# Vectr.net
KiCad netlist of a schematic drawn in EAGLE
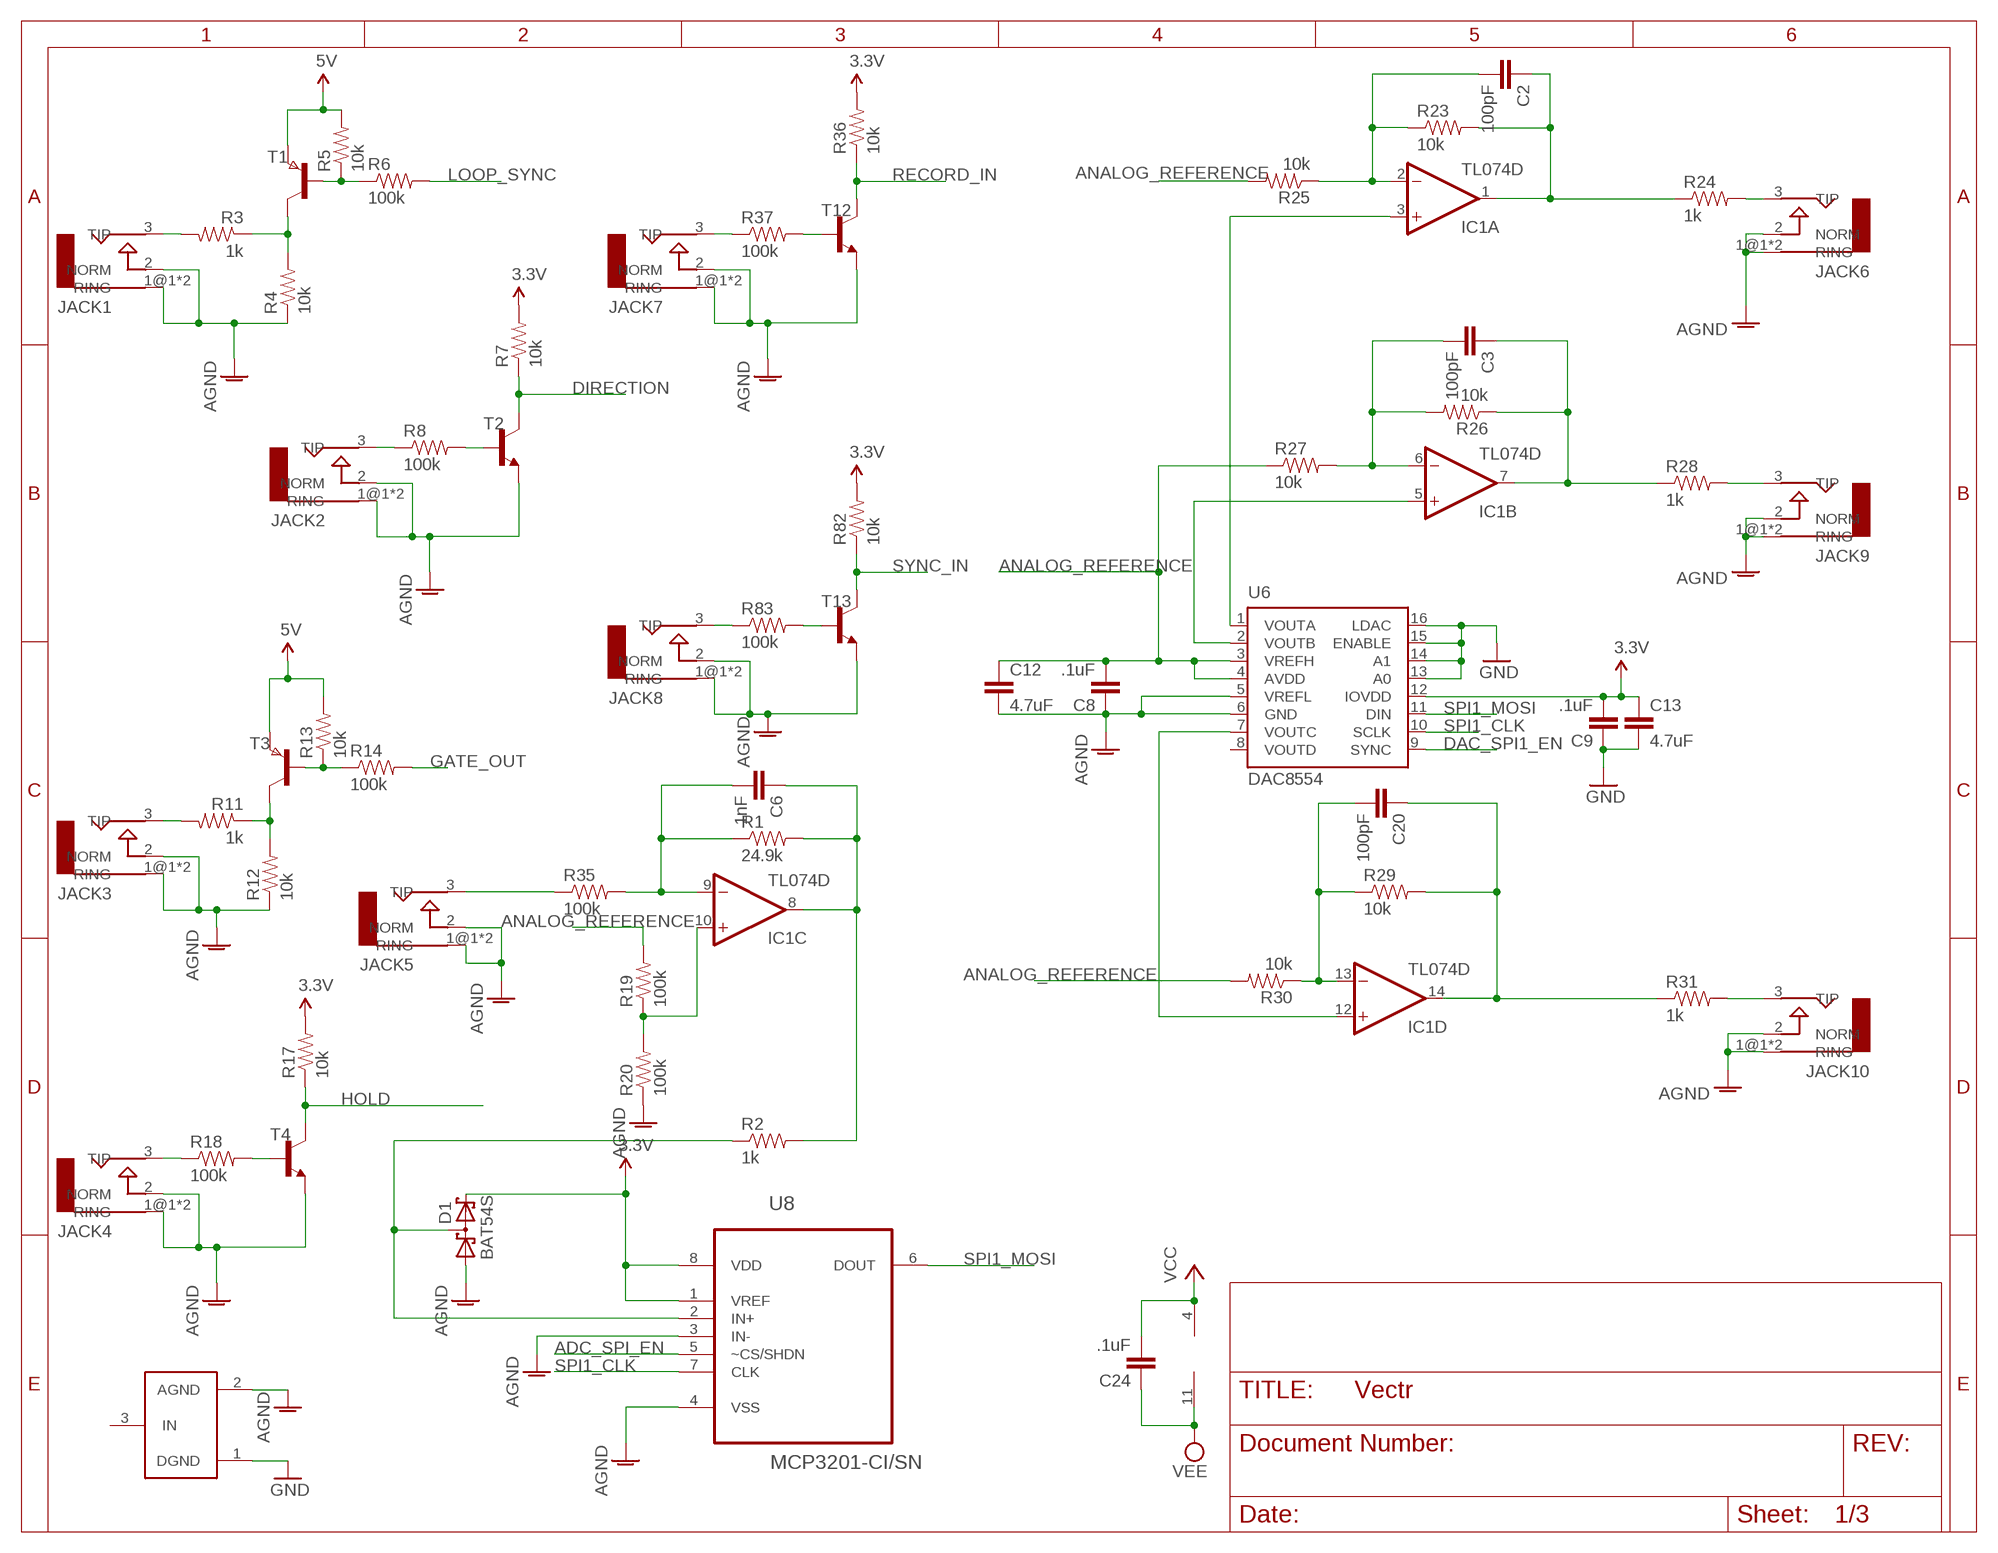
[diagram p0: schematic, sheet 1]
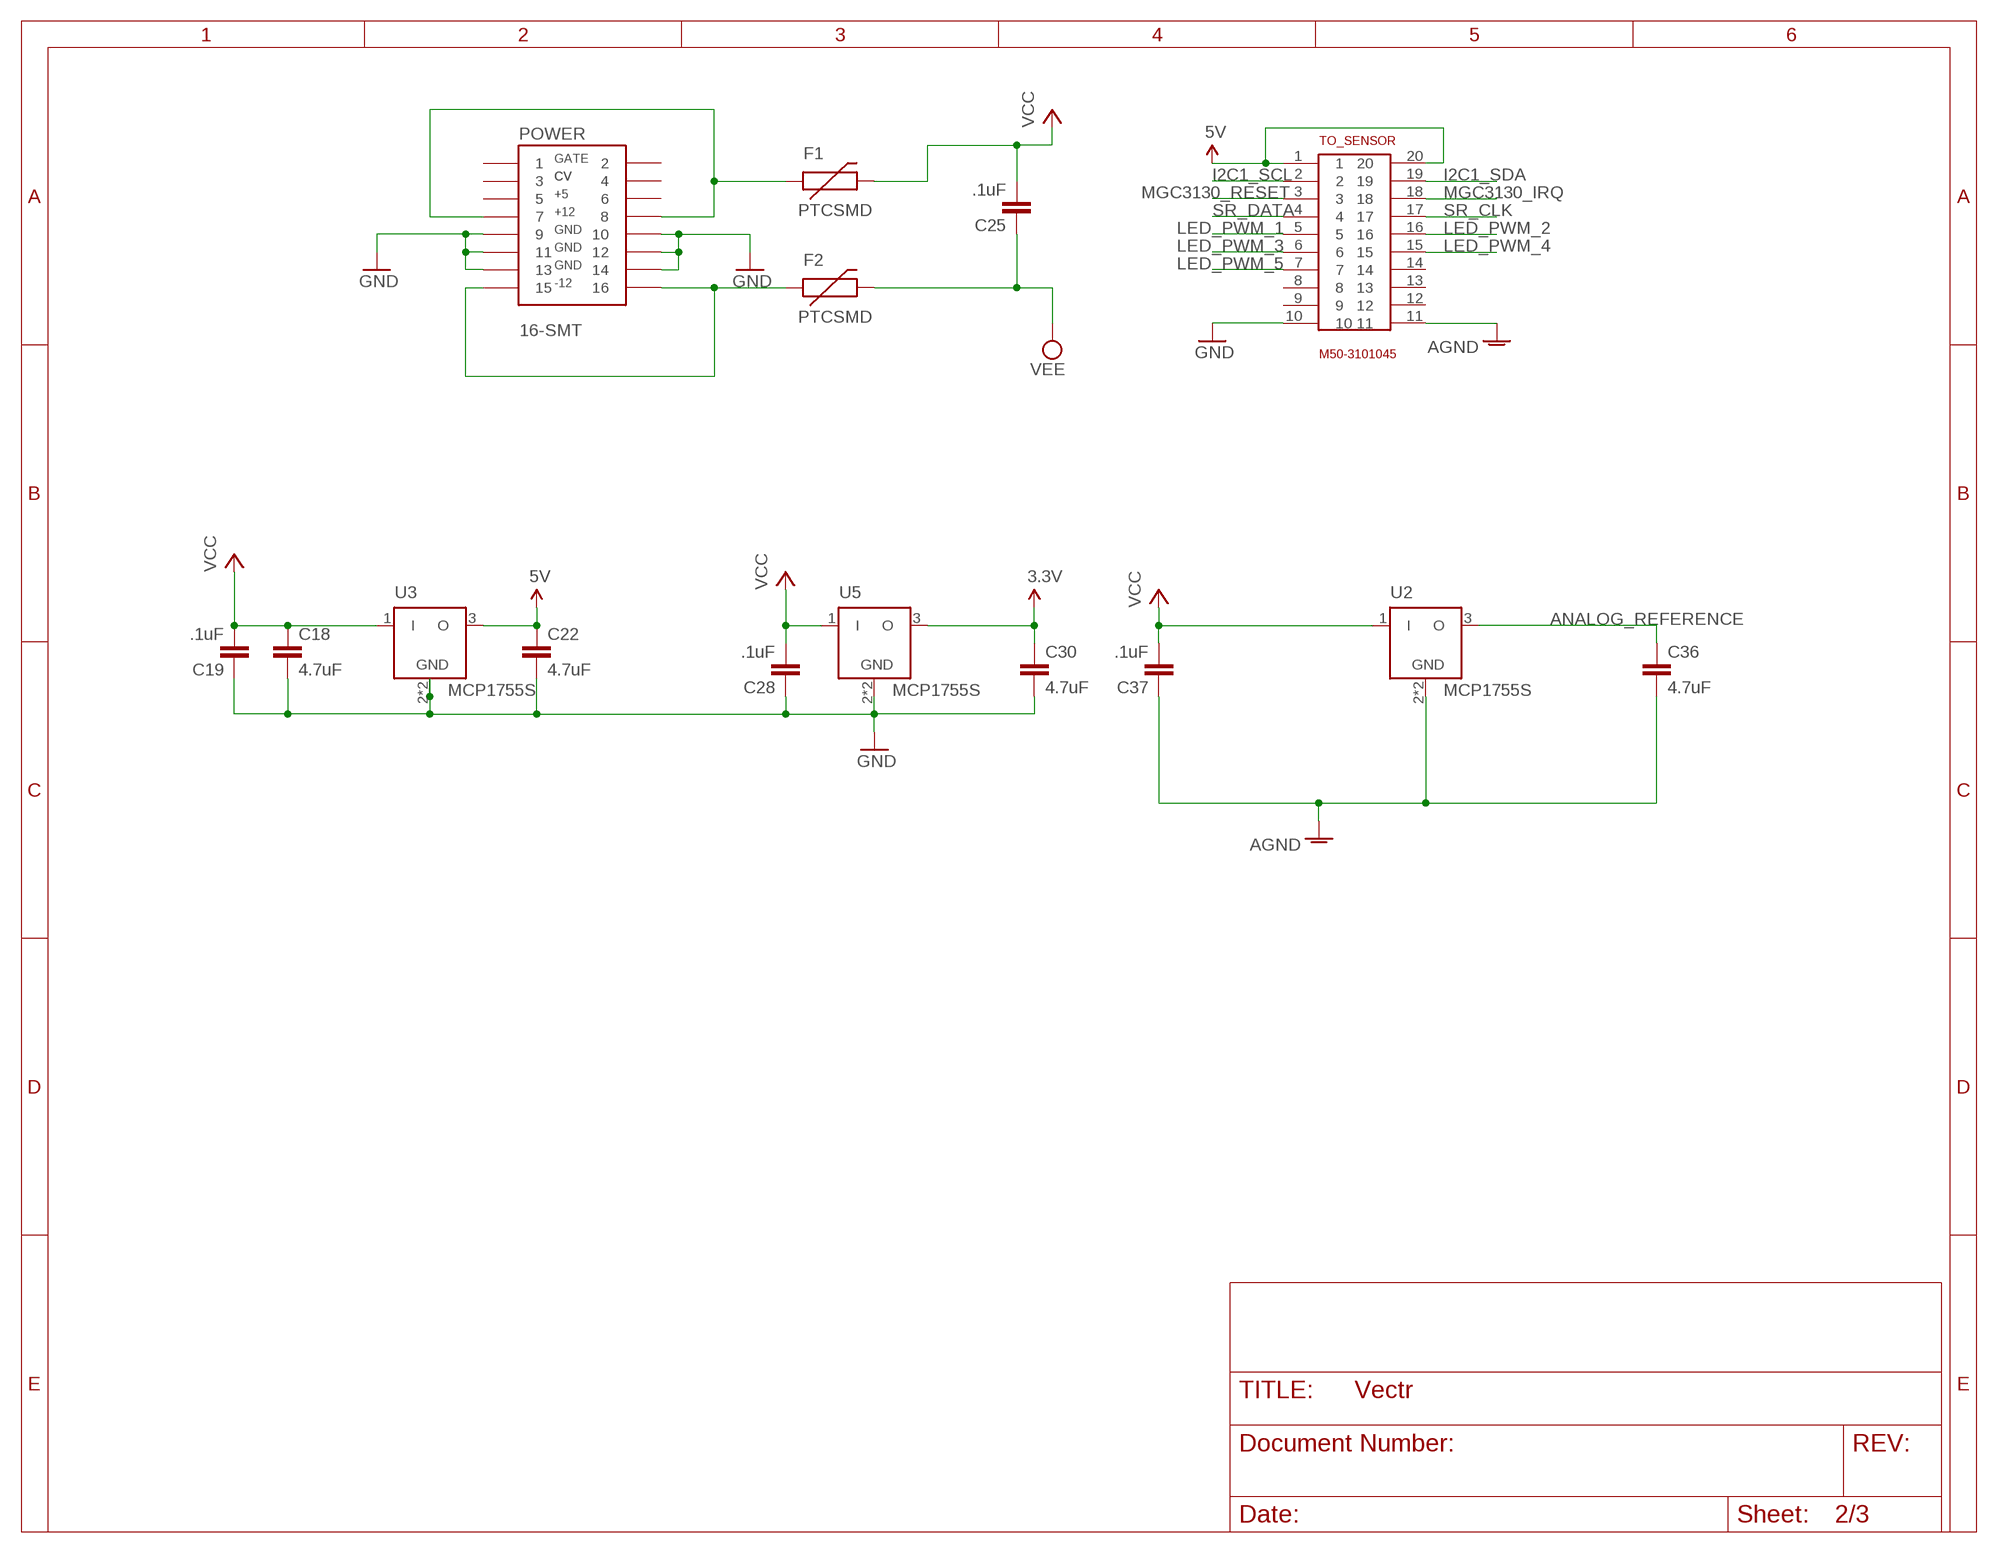
[diagram p1: schematic, sheet 2]
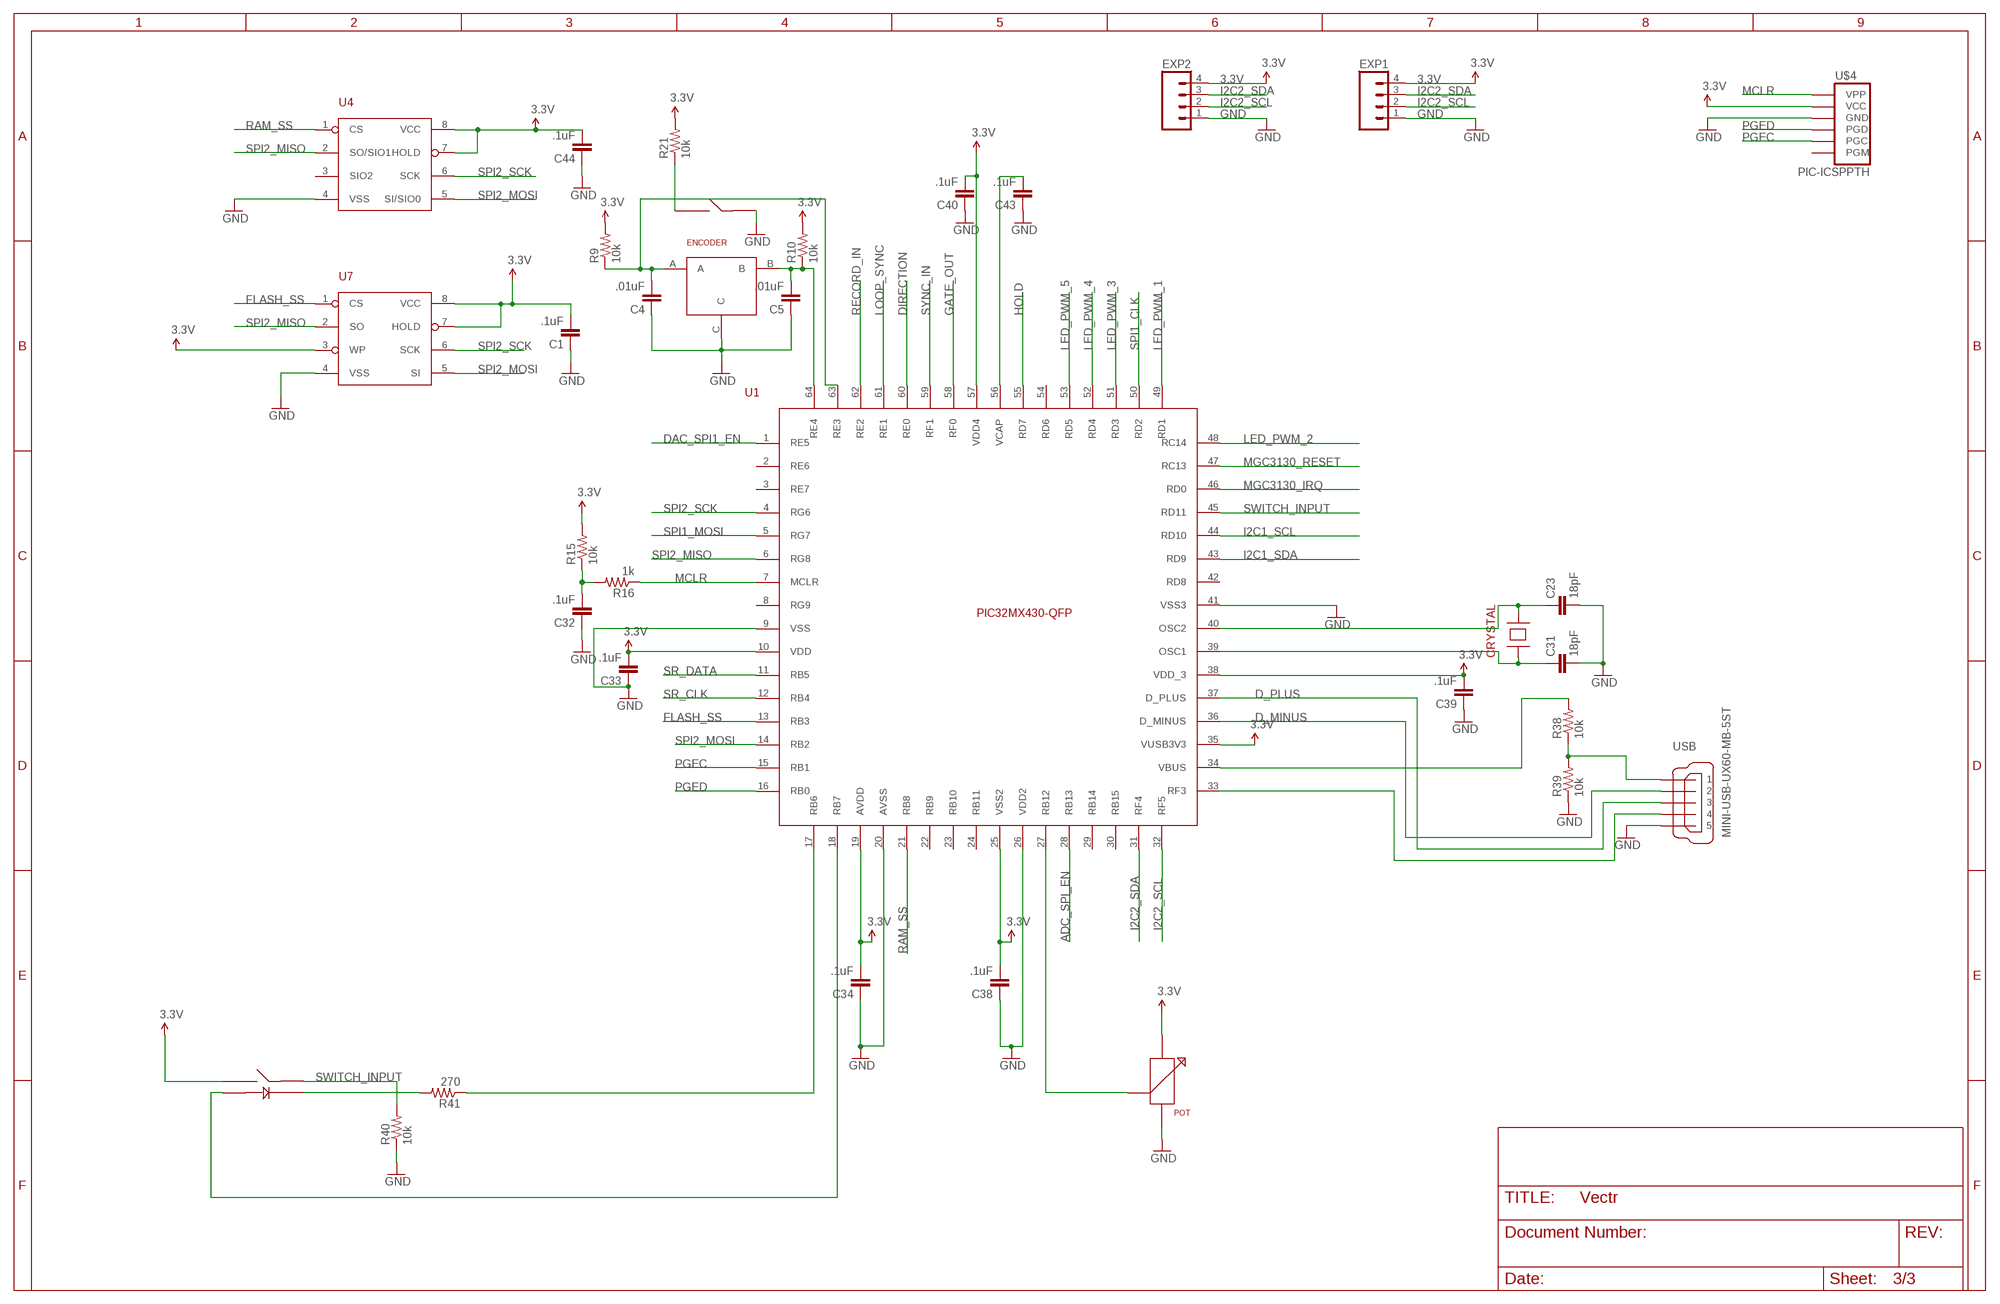
[diagram p2: schematic, sheet 3]

(export (version "E")
  (design (tool "Eeschema 10.0.6"))
  (components
    (comp (ref "C1")
      (value ".1uF")
      (footprint "eagle-import:0603-CAP")
      (libsource (lib "eagle-import") (part "SparkFun-Passives_CAP0603-CAP"))
    )
    (comp (ref "C4")
      (value ".01uF")
      (footprint "eagle-import:0603-CAP")
      (libsource (lib "eagle-import") (part "SparkFun-Passives_CAP0603-CAP"))
    )
    (comp (ref "C5")
      (value ".01uF")
      (footprint "eagle-import:0603-CAP")
      (libsource (lib "eagle-import") (part "SparkFun-Passives_CAP0603-CAP"))
    )
    (comp (ref "C23")
      (value "18pF")
      (footprint "eagle-import:0603-CAP")
      (libsource (lib "eagle-import") (part "SparkFun-Passives_CAP0603-CAP"))
    )
    (comp (ref "C31")
      (value "18pF")
      (footprint "eagle-import:0603-CAP")
      (libsource (lib "eagle-import") (part "SparkFun-Passives_CAP0603-CAP"))
    )
    (comp (ref "C32")
      (value ".1uF")
      (footprint "eagle-import:0603-CAP")
      (libsource (lib "eagle-import") (part "SparkFun-Passives_CAP0603-CAP"))
    )
    (comp (ref "C33")
      (value ".1uF")
      (footprint "eagle-import:0603-CAP")
      (libsource (lib "eagle-import") (part "SparkFun-Passives_CAP0603-CAP"))
    )
    (comp (ref "C34")
      (value ".1uF")
      (footprint "eagle-import:0603-CAP")
      (libsource (lib "eagle-import") (part "SparkFun-Passives_CAP0603-CAP"))
    )
    (comp (ref "C38")
      (value ".1uF")
      (footprint "eagle-import:0603-CAP")
      (libsource (lib "eagle-import") (part "SparkFun-Passives_CAP0603-CAP"))
    )
    (comp (ref "C39")
      (value ".1uF")
      (footprint "eagle-import:0603-CAP")
      (libsource (lib "eagle-import") (part "SparkFun-Passives_CAP0603-CAP"))
    )
    (comp (ref "C40")
      (value ".1uF")
      (footprint "eagle-import:0603-CAP")
      (libsource (lib "eagle-import") (part "SparkFun-Passives_CAP0603-CAP"))
    )
    (comp (ref "C43")
      (value ".1uF")
      (footprint "eagle-import:0603-CAP")
      (libsource (lib "eagle-import") (part "SparkFun-Passives_CAP0603-CAP"))
    )
    (comp (ref "C44")
      (value ".1uF")
      (footprint "eagle-import:0603-CAP")
      (libsource (lib "eagle-import") (part "SparkFun-Passives_CAP0603-CAP"))
    )
    (comp (ref "CRYSTAL")
      (value "SMD-4-CRYSTAL")
      (footprint "eagle-import:SMD-4-CRYSTAL")
      (libsource (lib "eagle-import") (part "SMD-4-CRYSTAL"))
    )
    (comp (ref "ENCODER")
      (value "PEC16_ENCODER")
      (footprint "eagle-import:PEC16_ENCODER")
      (libsource (lib "eagle-import") (part "PEC16_ENCODER"))
    )
    (comp (ref "EXP1")
      (value "M04SMD_STRAIGHT_COMBO")
      (footprint "eagle-import:1X04_SMD_STRAIGHT_COMBO")
      (libsource (lib "eagle-import") (part "M04SMD_STRAIGHT_COMBO"))
    )
    (comp (ref "EXP2")
      (value "M04SMD_STRAIGHT_COMBO")
      (footprint "eagle-import:1X04_SMD_STRAIGHT_COMBO")
      (libsource (lib "eagle-import") (part "M04SMD_STRAIGHT_COMBO"))
    )
    (comp (ref "POT")
      (value "9MMPOT")
      (footprint "eagle-import:9MMPOT")
      (libsource (lib "eagle-import") (part "9MMPOT"))
    )
    (comp (ref "R9")
      (value "10k")
      (footprint "eagle-import:0603-RES")
      (libsource (lib "eagle-import") (part "RESISTOR0603-RES"))
    )
    (comp (ref "R10")
      (value "10k")
      (footprint "eagle-import:0603-RES")
      (libsource (lib "eagle-import") (part "RESISTOR0603-RES"))
    )
    (comp (ref "R15")
      (value "10k")
      (footprint "eagle-import:0603-RES")
      (libsource (lib "eagle-import") (part "RESISTOR0603-RES"))
    )
    (comp (ref "R16")
      (value "1k")
      (footprint "eagle-import:0603-RES")
      (libsource (lib "eagle-import") (part "RESISTOR0603-RES"))
    )
    (comp (ref "R21")
      (value "10k")
      (footprint "eagle-import:0603-RES")
      (libsource (lib "eagle-import") (part "RESISTOR0603-RES"))
    )
    (comp (ref "R38")
      (value "10k")
      (footprint "eagle-import:0603-RES")
      (libsource (lib "eagle-import") (part "RESISTOR0603-RES"))
    )
    (comp (ref "R39")
      (value "10k")
      (footprint "eagle-import:0603-RES")
      (libsource (lib "eagle-import") (part "RESISTOR0603-RES"))
    )
    (comp (ref "R40")
      (value "10k")
      (footprint "eagle-import:0603-RES")
      (libsource (lib "eagle-import") (part "RESISTOR0603-RES"))
    )
    (comp (ref "R41")
      (value "270")
      (footprint "eagle-import:0603-RES")
      (libsource (lib "eagle-import") (part "RESISTOR0603-RES"))
    )
    (comp (ref "U$2")
      (value "5GSH9")
      (footprint "eagle-import:5GSH9")
      (libsource (lib "eagle-import") (part "5GSH9"))
    )
    (comp (ref "U$4")
      (value "PIC-ICSPPTH")
      (footprint "eagle-import:MOLEX-1X6")
      (libsource (lib "eagle-import") (part "PIC-ICSPPTH"))
    )
    (comp (ref "U1")
      (value "PIC32MX430-QFP")
      (footprint "eagle-import:QFP50P1200X1200X120-64N")
      (libsource (lib "eagle-import") (part "PIC32MX430-QFP"))
    )
    (comp (ref "U4")
      (value "23LC512")
      (footprint "eagle-import:SO-08")
      (libsource (lib "eagle-import") (part "23LC512"))
    )
    (comp (ref "U7")
      (value "SST25VF010A")
      (footprint "eagle-import:SO-08")
      (libsource (lib "eagle-import") (part "SST25VF010A"))
    )
    (comp (ref "USB")
      (value "MINI-USB-UX60-MB-5ST")
      (footprint "eagle-import:UX60-MB-5ST")
      (libsource (lib "eagle-import") (part "MINI-USB-UX60-MB-5ST"))
    )
    (comp (ref "C18")
      (value "4.7uF")
      (footprint "eagle-import:1206")
      (libsource (lib "eagle-import") (part "CAP1206"))
    )
    (comp (ref "C19")
      (value ".1uF")
      (footprint "eagle-import:0603-CAP")
      (libsource (lib "eagle-import") (part "SparkFun-Passives_CAP0603-CAP"))
    )
    (comp (ref "C22")
      (value "4.7uF")
      (footprint "eagle-import:1206")
      (libsource (lib "eagle-import") (part "CAP1206"))
    )
    (comp (ref "C25")
      (value ".1uF")
      (footprint "eagle-import:0603-CAP")
      (libsource (lib "eagle-import") (part "SparkFun-Passives_CAP0603-CAP"))
    )
    (comp (ref "C28")
      (value ".1uF")
      (footprint "eagle-import:0603-CAP")
      (libsource (lib "eagle-import") (part "SparkFun-Passives_CAP0603-CAP"))
    )
    (comp (ref "C30")
      (value "4.7uF")
      (footprint "eagle-import:1206")
      (libsource (lib "eagle-import") (part "CAP1206"))
    )
    (comp (ref "C36")
      (value "4.7uF")
      (footprint "eagle-import:1206")
      (libsource (lib "eagle-import") (part "CAP1206"))
    )
    (comp (ref "C37")
      (value ".1uF")
      (footprint "eagle-import:0603-CAP")
      (libsource (lib "eagle-import") (part "SparkFun-Passives_CAP0603-CAP"))
    )
    (comp (ref "F1")
      (value "PTCSMD")
      (footprint "eagle-import:PTC-1206")
      (libsource (lib "eagle-import") (part "PTCSMD"))
    )
    (comp (ref "F2")
      (value "PTCSMD")
      (footprint "eagle-import:PTC-1206")
      (libsource (lib "eagle-import") (part "PTCSMD"))
    )
    (comp (ref "POWER")
      (value "16-SMT")
      (footprint "eagle-import:16-SMT")
      (libsource (lib "eagle-import") (part "16-SMT"))
    )
    (comp (ref "TO_SENSOR")
      (value "M50-3101045")
      (footprint "eagle-import:M50-3101045")
      (libsource (lib "eagle-import") (part "M50-3101045"))
    )
    (comp (ref "U2")
      (value "MCP1755S")
      (footprint "eagle-import:SOT223")
      (libsource (lib "eagle-import") (part "MCP1755S"))
    )
    (comp (ref "U3")
      (value "MCP1755S")
      (footprint "eagle-import:SOT223")
      (libsource (lib "eagle-import") (part "MCP1755S"))
    )
    (comp (ref "U5")
      (value "MCP1755S")
      (footprint "eagle-import:SOT223")
      (libsource (lib "eagle-import") (part "MCP1755S"))
    )
    (comp (ref "C2")
      (value "100pF")
      (footprint "eagle-import:0603-CAP")
      (libsource (lib "eagle-import") (part "SparkFun-Passives_CAP0603-CAP"))
    )
    (comp (ref "C3")
      (value "100pF")
      (footprint "eagle-import:0603-CAP")
      (libsource (lib "eagle-import") (part "SparkFun-Passives_CAP0603-CAP"))
    )
    (comp (ref "C6")
      (value "1nF")
      (footprint "eagle-import:0603-CAP")
      (libsource (lib "eagle-import") (part "SparkFun-Passives_CAP0603-CAP"))
    )
    (comp (ref "C8")
      (value ".1uF")
      (footprint "eagle-import:0603-CAP")
      (libsource (lib "eagle-import") (part "SparkFun-Passives_CAP0603-CAP"))
    )
    (comp (ref "C9")
      (value ".1uF")
      (footprint "eagle-import:0603-CAP")
      (libsource (lib "eagle-import") (part "SparkFun-Passives_CAP0603-CAP"))
    )
    (comp (ref "C12")
      (value "4.7uF")
      (footprint "eagle-import:1206")
      (libsource (lib "eagle-import") (part "CAP1206"))
    )
    (comp (ref "C13")
      (value "4.7uF")
      (footprint "eagle-import:1206")
      (libsource (lib "eagle-import") (part "CAP1206"))
    )
    (comp (ref "C20")
      (value "100pF")
      (footprint "eagle-import:0603-CAP")
      (libsource (lib "eagle-import") (part "SparkFun-Passives_CAP0603-CAP"))
    )
    (comp (ref "C24")
      (value ".1uF")
      (footprint "eagle-import:0603-CAP")
      (libsource (lib "eagle-import") (part "SparkFun-Passives_CAP0603-CAP"))
    )
    (comp (ref "D1")
      (value "BAT54S")
      (footprint "eagle-import:SOT23")
      (libsource (lib "eagle-import") (part "BAT54S"))
    )
    (comp (ref "IC1")
      (value "TL074D")
      (footprint "eagle-import:SO14")
      (libsource (lib "eagle-import") (part "TL074D"))
    )
    (comp (ref "JACK1")
      (value "AUDIO-JACKERTHENVAR")
      (footprint "eagle-import:ERTHENVAR-JACK")
      (libsource (lib "eagle-import") (part "AUDIO-JACKERTHENVAR"))
    )
    (comp (ref "JACK2")
      (value "AUDIO-JACKERTHENVAR")
      (footprint "eagle-import:ERTHENVAR-JACK")
      (libsource (lib "eagle-import") (part "AUDIO-JACKERTHENVAR"))
    )
    (comp (ref "JACK3")
      (value "AUDIO-JACKERTHENVAR")
      (footprint "eagle-import:ERTHENVAR-JACK")
      (libsource (lib "eagle-import") (part "AUDIO-JACKERTHENVAR"))
    )
    (comp (ref "JACK4")
      (value "AUDIO-JACKERTHENVAR")
      (footprint "eagle-import:ERTHENVAR-JACK")
      (libsource (lib "eagle-import") (part "AUDIO-JACKERTHENVAR"))
    )
    (comp (ref "JACK5")
      (value "AUDIO-JACKERTHENVAR")
      (footprint "eagle-import:ERTHENVAR-JACK")
      (libsource (lib "eagle-import") (part "AUDIO-JACKERTHENVAR"))
    )
    (comp (ref "JACK6")
      (value "AUDIO-JACKERTHENVAR")
      (footprint "eagle-import:ERTHENVAR-JACK")
      (libsource (lib "eagle-import") (part "AUDIO-JACKERTHENVAR"))
    )
    (comp (ref "JACK7")
      (value "AUDIO-JACKERTHENVAR")
      (footprint "eagle-import:ERTHENVAR-JACK")
      (libsource (lib "eagle-import") (part "AUDIO-JACKERTHENVAR"))
    )
    (comp (ref "JACK8")
      (value "AUDIO-JACKERTHENVAR")
      (footprint "eagle-import:ERTHENVAR-JACK")
      (libsource (lib "eagle-import") (part "AUDIO-JACKERTHENVAR"))
    )
    (comp (ref "JACK9")
      (value "AUDIO-JACKERTHENVAR")
      (footprint "eagle-import:ERTHENVAR-JACK")
      (libsource (lib "eagle-import") (part "AUDIO-JACKERTHENVAR"))
    )
    (comp (ref "JACK10")
      (value "AUDIO-JACKERTHENVAR")
      (footprint "eagle-import:ERTHENVAR-JACK")
      (libsource (lib "eagle-import") (part "AUDIO-JACKERTHENVAR"))
    )
    (comp (ref "R1")
      (value "24.9k")
      (footprint "eagle-import:0603-RES")
      (libsource (lib "eagle-import") (part "RESISTOR0603-RES"))
    )
    (comp (ref "R2")
      (value "1k")
      (footprint "eagle-import:0603-RES")
      (libsource (lib "eagle-import") (part "RESISTOR0603-RES"))
    )
    (comp (ref "R3")
      (value "1k")
      (footprint "eagle-import:0603-RES")
      (libsource (lib "eagle-import") (part "RESISTOR0603-RES"))
    )
    (comp (ref "R4")
      (value "10k")
      (footprint "eagle-import:0603-RES")
      (libsource (lib "eagle-import") (part "RESISTOR0603-RES"))
    )
    (comp (ref "R5")
      (value "10k")
      (footprint "eagle-import:0603-RES")
      (libsource (lib "eagle-import") (part "RESISTOR0603-RES"))
    )
    (comp (ref "R6")
      (value "100k")
      (footprint "eagle-import:0603-RES")
      (libsource (lib "eagle-import") (part "RESISTOR0603-RES"))
    )
    (comp (ref "R7")
      (value "10k")
      (footprint "eagle-import:0603-RES")
      (libsource (lib "eagle-import") (part "RESISTOR0603-RES"))
    )
    (comp (ref "R8")
      (value "100k")
      (footprint "eagle-import:0603-RES")
      (libsource (lib "eagle-import") (part "RESISTOR0603-RES"))
    )
    (comp (ref "R11")
      (value "1k")
      (footprint "eagle-import:0603-RES")
      (libsource (lib "eagle-import") (part "RESISTOR0603-RES"))
    )
    (comp (ref "R12")
      (value "10k")
      (footprint "eagle-import:0603-RES")
      (libsource (lib "eagle-import") (part "RESISTOR0603-RES"))
    )
    (comp (ref "R13")
      (value "10k")
      (footprint "eagle-import:0603-RES")
      (libsource (lib "eagle-import") (part "RESISTOR0603-RES"))
    )
    (comp (ref "R14")
      (value "100k")
      (footprint "eagle-import:0603-RES")
      (libsource (lib "eagle-import") (part "RESISTOR0603-RES"))
    )
    (comp (ref "R17")
      (value "10k")
      (footprint "eagle-import:0603-RES")
      (libsource (lib "eagle-import") (part "RESISTOR0603-RES"))
    )
    (comp (ref "R18")
      (value "100k")
      (footprint "eagle-import:0603-RES")
      (libsource (lib "eagle-import") (part "RESISTOR0603-RES"))
    )
    (comp (ref "R19")
      (value "100k")
      (footprint "eagle-import:0603-RES")
      (libsource (lib "eagle-import") (part "RESISTOR0603-RES"))
    )
    (comp (ref "R20")
      (value "100k")
      (footprint "eagle-import:0603-RES")
      (libsource (lib "eagle-import") (part "RESISTOR0603-RES"))
    )
    (comp (ref "R23")
      (value "10k")
      (footprint "eagle-import:0603-RES")
      (libsource (lib "eagle-import") (part "RESISTOR0603-RES"))
    )
    (comp (ref "R24")
      (value "1k")
      (footprint "eagle-import:0603-RES")
      (libsource (lib "eagle-import") (part "RESISTOR0603-RES"))
    )
    (comp (ref "R25")
      (value "10k")
      (footprint "eagle-import:0603-RES")
      (libsource (lib "eagle-import") (part "RESISTOR0603-RES"))
    )
    (comp (ref "R26")
      (value "10k")
      (footprint "eagle-import:0603-RES")
      (libsource (lib "eagle-import") (part "RESISTOR0603-RES"))
    )
    (comp (ref "R27")
      (value "10k")
      (footprint "eagle-import:0603-RES")
      (libsource (lib "eagle-import") (part "RESISTOR0603-RES"))
    )
    (comp (ref "R28")
      (value "1k")
      (footprint "eagle-import:0603-RES")
      (libsource (lib "eagle-import") (part "RESISTOR0603-RES"))
    )
    (comp (ref "R29")
      (value "10k")
      (footprint "eagle-import:0603-RES")
      (libsource (lib "eagle-import") (part "RESISTOR0603-RES"))
    )
    (comp (ref "R30")
      (value "10k")
      (footprint "eagle-import:0603-RES")
      (libsource (lib "eagle-import") (part "RESISTOR0603-RES"))
    )
    (comp (ref "R31")
      (value "1k")
      (footprint "eagle-import:0603-RES")
      (libsource (lib "eagle-import") (part "RESISTOR0603-RES"))
    )
    (comp (ref "R35")
      (value "100k")
      (footprint "eagle-import:0603-RES")
      (libsource (lib "eagle-import") (part "RESISTOR0603-RES"))
    )
    (comp (ref "R36")
      (value "10k")
      (footprint "eagle-import:0603-RES")
      (libsource (lib "eagle-import") (part "RESISTOR0603-RES"))
    )
    (comp (ref "R37")
      (value "100k")
      (footprint "eagle-import:0603-RES")
      (libsource (lib "eagle-import") (part "RESISTOR0603-RES"))
    )
    (comp (ref "R82")
      (value "10k")
      (footprint "eagle-import:0603-RES")
      (libsource (lib "eagle-import") (part "RESISTOR0603-RES"))
    )
    (comp (ref "R83")
      (value "100k")
      (footprint "eagle-import:0603-RES")
      (libsource (lib "eagle-import") (part "RESISTOR0603-RES"))
    )
    (comp (ref "T1")
      (value "PNPSOT23")
      (footprint "eagle-import:SOT-23")
      (fields (field (name "MPN") "DSS20200L-7"))
      (libsource (lib "eagle-import") (part "PNPSOT23"))
    )
    (comp (ref "T2")
      (value "-NPN-SOT23-EBC")
      (footprint "eagle-import:SOT23-EBC")
      (libsource (lib "eagle-import") (part "-NPN-SOT23-EBC"))
    )
    (comp (ref "T3")
      (value "PNPSOT23")
      (footprint "eagle-import:SOT-23")
      (fields (field (name "MPN") "DSS20200L-7"))
      (libsource (lib "eagle-import") (part "PNPSOT23"))
    )
    (comp (ref "T4")
      (value "-NPN-SOT23-EBC")
      (footprint "eagle-import:SOT23-EBC")
      (libsource (lib "eagle-import") (part "-NPN-SOT23-EBC"))
    )
    (comp (ref "T12")
      (value "-NPN-SOT23-EBC")
      (footprint "eagle-import:SOT23-EBC")
      (libsource (lib "eagle-import") (part "-NPN-SOT23-EBC"))
    )
    (comp (ref "T13")
      (value "-NPN-SOT23-EBC")
      (footprint "eagle-import:SOT23-EBC")
      (libsource (lib "eagle-import") (part "-NPN-SOT23-EBC"))
    )
    (comp (ref "U$11")
      (value "GND_CONNECT")
      (footprint "eagle-import:GND_CONNECT")
      (libsource (lib "eagle-import") (part "GND_CONNECT"))
    )
    (comp (ref "U6")
      (value "DAC8554")
      (footprint "eagle-import:PW_R-PDSO-G16")
      (libsource (lib "eagle-import") (part "DAC8554"))
    )
    (comp (ref "U8")
      (value "MCP3201-CI/SN")
      (footprint "eagle-import:SOIC127P600X175-8N")
      (libsource (lib "eagle-import") (part "MCP3201-CI/SN"))
    )
  )
  (nets
    (net (code "1") (name "3.3V") (class "Default")
      (node (ref "C1") (pin "2") (pinfunction "2_2") (pintype "passive"))
      (node (ref "C13") (pin "1") (pinfunction "1_1") (pintype "passive"))
      (node (ref "C30") (pin "1") (pinfunction "1_1") (pintype "passive"))
      (node (ref "C33") (pin "2") (pinfunction "2_2") (pintype "passive"))
      (node (ref "C34") (pin "2") (pinfunction "2_2") (pintype "passive"))
      (node (ref "C38") (pin "2") (pinfunction "2_2") (pintype "passive"))
      (node (ref "C39") (pin "2") (pinfunction "2_2") (pintype "passive"))
      (node (ref "C40") (pin "2") (pinfunction "2_2") (pintype "passive"))
      (node (ref "C44") (pin "2") (pinfunction "2_2") (pintype "passive"))
      (node (ref "C9") (pin "2") (pinfunction "2_2") (pintype "passive"))
      (node (ref "D1") (pin "2") (pinfunction "C2_2") (pintype "passive"))
      (node (ref "EXP1") (pin "4") (pinfunction "4_4") (pintype "passive"))
      (node (ref "EXP2") (pin "4") (pinfunction "4_4") (pintype "passive"))
      (node (ref "POT") (pin "1") (pinfunction "1_1") (pintype "bidirectional"))
      (node (ref "R10") (pin "2") (pinfunction "2_2") (pintype "passive"))
      (node (ref "R15") (pin "2") (pinfunction "2_2") (pintype "passive"))
      (node (ref "R17") (pin "2") (pinfunction "2_2") (pintype "passive"))
      (node (ref "R21") (pin "2") (pinfunction "2_2") (pintype "passive"))
      (node (ref "R36") (pin "2") (pinfunction "2_2") (pintype "passive"))
      (node (ref "R7") (pin "2") (pinfunction "2_2") (pintype "passive"))
      (node (ref "R82") (pin "2") (pinfunction "2_2") (pintype "passive"))
      (node (ref "R9") (pin "2") (pinfunction "2_2") (pintype "passive"))
      (node (ref "U$2") (pin "1") (pinfunction "1_1") (pintype "bidirectional"))
      (node (ref "U$4") (pin "5") (pinfunction "VCC_5") (pintype "bidirectional"))
      (node (ref "U1") (pin "10") (pinfunction "VDD_10") (pintype "bidirectional"))
      (node (ref "U1") (pin "19") (pinfunction "AVDD_19") (pintype "bidirectional"))
      (node (ref "U1") (pin "25") (pinfunction "VSS2_25") (pintype "bidirectional"))
      (node (ref "U1") (pin "35") (pinfunction "VUSB3V3_35") (pintype "bidirectional"))
      (node (ref "U1") (pin "38") (pinfunction "VDD_3_38") (pintype "bidirectional"))
      (node (ref "U1") (pin "57") (pinfunction "VDD4_57") (pintype "bidirectional"))
      (node (ref "U4") (pin "7") (pinfunction "HOLD_7") (pintype "bidirectional"))
      (node (ref "U4") (pin "8") (pinfunction "VCC_8") (pintype "power_in"))
      (node (ref "U5") (pin "3") (pinfunction "O_3") (pintype "input"))
      (node (ref "U6") (pin "12") (pinfunction "IOVDD_12") (pintype "input"))
      (node (ref "U7") (pin "3") (pinfunction "WP_3") (pintype "bidirectional"))
      (node (ref "U7") (pin "7") (pinfunction "HOLD_7") (pintype "bidirectional"))
      (node (ref "U7") (pin "8") (pinfunction "VCC_8") (pintype "power_in"))
      (node (ref "U8") (pin "1") (pinfunction "VREF_1") (pintype "input"))
      (node (ref "U8") (pin "8") (pinfunction "VDD_8") (pintype "power_in"))
    )
    (net (code "2") (name "5V") (class "Default")
      (node (ref "C22") (pin "1") (pinfunction "1_1") (pintype "passive"))
      (node (ref "R13") (pin "2") (pinfunction "2_2") (pintype "passive"))
      (node (ref "R5") (pin "2") (pinfunction "2_2") (pintype "passive"))
      (node (ref "T1") (pin "2") (pinfunction "E_2") (pintype "passive"))
      (node (ref "T3") (pin "2") (pinfunction "E_2") (pintype "passive"))
      (node (ref "TO_SENSOR") (pin "1") (pinfunction "1_1") (pintype "bidirectional"))
      (node (ref "TO_SENSOR") (pin "20") (pinfunction "20_20") (pintype "bidirectional"))
      (node (ref "U3") (pin "3") (pinfunction "O_3") (pintype "input"))
    )
    (net (code "3") (name "ADC_SPI_EN") (class "Default")
      (node (ref "U1") (pin "28") (pinfunction "RB13_28") (pintype "bidirectional"))
      (node (ref "U8") (pin "5") (pinfunction "~{CS/SHDN}_5") (pintype "input"))
    )
    (net (code "4") (name "AGND") (class "Default")
      (node (ref "C12") (pin "2") (pinfunction "2_2") (pintype "passive"))
      (node (ref "C36") (pin "2") (pinfunction "2_2") (pintype "passive"))
      (node (ref "C37") (pin "1") (pinfunction "1_1") (pintype "passive"))
      (node (ref "C8") (pin "1") (pinfunction "1_1") (pintype "passive"))
      (node (ref "D1") (pin "1") (pinfunction "A1_1") (pintype "passive"))
      (node (ref "JACK1") (pin "1@1") (pinfunction "RING_1@1") (pintype "bidirectional"))
      (node (ref "JACK1") (pin "1@2") (pinfunction "RING_1@2") (pintype "bidirectional"))
      (node (ref "JACK1") (pin "2") (pinfunction "NORM_2") (pintype "bidirectional"))
      (node (ref "JACK10") (pin "1@1") (pinfunction "RING_1@1") (pintype "bidirectional"))
      (node (ref "JACK10") (pin "1@2") (pinfunction "RING_1@2") (pintype "bidirectional"))
      (node (ref "JACK10") (pin "2") (pinfunction "NORM_2") (pintype "bidirectional"))
      (node (ref "JACK2") (pin "1@1") (pinfunction "RING_1@1") (pintype "bidirectional"))
      (node (ref "JACK2") (pin "1@2") (pinfunction "RING_1@2") (pintype "bidirectional"))
      (node (ref "JACK2") (pin "2") (pinfunction "NORM_2") (pintype "bidirectional"))
      (node (ref "JACK3") (pin "1@1") (pinfunction "RING_1@1") (pintype "bidirectional"))
      (node (ref "JACK3") (pin "1@2") (pinfunction "RING_1@2") (pintype "bidirectional"))
      (node (ref "JACK3") (pin "2") (pinfunction "NORM_2") (pintype "bidirectional"))
      (node (ref "JACK4") (pin "1@1") (pinfunction "RING_1@1") (pintype "bidirectional"))
      (node (ref "JACK4") (pin "1@2") (pinfunction "RING_1@2") (pintype "bidirectional"))
      (node (ref "JACK4") (pin "2") (pinfunction "NORM_2") (pintype "bidirectional"))
      (node (ref "JACK5") (pin "1@1") (pinfunction "RING_1@1") (pintype "bidirectional"))
      (node (ref "JACK5") (pin "1@2") (pinfunction "RING_1@2") (pintype "bidirectional"))
      (node (ref "JACK5") (pin "2") (pinfunction "NORM_2") (pintype "bidirectional"))
      (node (ref "JACK6") (pin "1@1") (pinfunction "RING_1@1") (pintype "bidirectional"))
      (node (ref "JACK6") (pin "1@2") (pinfunction "RING_1@2") (pintype "bidirectional"))
      (node (ref "JACK6") (pin "2") (pinfunction "NORM_2") (pintype "bidirectional"))
      (node (ref "JACK7") (pin "1@1") (pinfunction "RING_1@1") (pintype "bidirectional"))
      (node (ref "JACK7") (pin "1@2") (pinfunction "RING_1@2") (pintype "bidirectional"))
      (node (ref "JACK7") (pin "2") (pinfunction "NORM_2") (pintype "bidirectional"))
      (node (ref "JACK8") (pin "1@1") (pinfunction "RING_1@1") (pintype "bidirectional"))
      (node (ref "JACK8") (pin "1@2") (pinfunction "RING_1@2") (pintype "bidirectional"))
      (node (ref "JACK8") (pin "2") (pinfunction "NORM_2") (pintype "bidirectional"))
      (node (ref "JACK9") (pin "1@1") (pinfunction "RING_1@1") (pintype "bidirectional"))
      (node (ref "JACK9") (pin "1@2") (pinfunction "RING_1@2") (pintype "bidirectional"))
      (node (ref "JACK9") (pin "2") (pinfunction "NORM_2") (pintype "bidirectional"))
      (node (ref "R12") (pin "1") (pinfunction "1_1") (pintype "passive"))
      (node (ref "R20") (pin "1") (pinfunction "1_1") (pintype "passive"))
      (node (ref "R4") (pin "1") (pinfunction "1_1") (pintype "passive"))
      (node (ref "T12") (pin "E") (pinfunction "E_E") (pintype "passive"))
      (node (ref "T13") (pin "E") (pinfunction "E_E") (pintype "passive"))
      (node (ref "T2") (pin "E") (pinfunction "E_E") (pintype "passive"))
      (node (ref "T4") (pin "E") (pinfunction "E_E") (pintype "passive"))
      (node (ref "TO_SENSOR") (pin "11") (pinfunction "11_11") (pintype "bidirectional"))
      (node (ref "U$11") (pin "2") (pinfunction "AGND_2") (pintype "bidirectional"))
      (node (ref "U2") (pin "2") (pinfunction "GND_2") (pintype "power_in"))
      (node (ref "U2") (pin "4") (pinfunction "GND_4") (pintype "power_in"))
      (node (ref "U6") (pin "5") (pinfunction "VREFL_5") (pintype "input"))
      (node (ref "U6") (pin "6") (pinfunction "GND_6") (pintype "input"))
      (node (ref "U8") (pin "3") (pinfunction "IN-_3") (pintype "input"))
      (node (ref "U8") (pin "4") (pinfunction "VSS_4") (pintype "power_in"))
    )
    (net (code "5") (name "ANALOG_REFERENCE") (class "Default")
      (node (ref "C12") (pin "1") (pinfunction "1_1") (pintype "passive"))
      (node (ref "C36") (pin "1") (pinfunction "1_1") (pintype "passive"))
      (node (ref "C8") (pin "2") (pinfunction "2_2") (pintype "passive"))
      (node (ref "R19") (pin "2") (pinfunction "2_2") (pintype "passive"))
      (node (ref "R25") (pin "2") (pinfunction "2_2") (pintype "passive"))
      (node (ref "R27") (pin "1") (pinfunction "1_1") (pintype "passive"))
      (node (ref "R30") (pin "2") (pinfunction "2_2") (pintype "passive"))
      (node (ref "U2") (pin "3") (pinfunction "O_3") (pintype "input"))
      (node (ref "U6") (pin "3") (pinfunction "VREFH_3") (pintype "input"))
      (node (ref "U6") (pin "4") (pinfunction "AVDD_4") (pintype "input"))
    )
    (net (code "6") (name "DAC_SPI1_EN") (class "Default")
      (node (ref "U1") (pin "1") (pinfunction "RE5_1") (pintype "bidirectional"))
      (node (ref "U6") (pin "9") (pinfunction "SYNC_9") (pintype "input"))
    )
    (net (code "7") (name "DIRECTION") (class "Default")
      (node (ref "R7") (pin "1") (pinfunction "1_1") (pintype "passive"))
      (node (ref "T2") (pin "C") (pinfunction "C_C") (pintype "passive"))
      (node (ref "U1") (pin "60") (pinfunction "RE0_60") (pintype "bidirectional"))
    )
    (net (code "8") (name "D_MINUS") (class "Default")
      (node (ref "U1") (pin "36") (pinfunction "D_MINUS_36") (pintype "bidirectional"))
      (node (ref "USB") (pin "2") (pinfunction "2_2") (pintype "input"))
    )
    (net (code "9") (name "D_PLUS") (class "Default")
      (node (ref "U1") (pin "37") (pinfunction "D_PLUS_37") (pintype "bidirectional"))
      (node (ref "USB") (pin "3") (pinfunction "3_3") (pintype "input"))
    )
    (net (code "10") (name "FLASH_SS") (class "Default")
      (node (ref "U1") (pin "13") (pinfunction "RB3_13") (pintype "bidirectional"))
      (node (ref "U7") (pin "1") (pinfunction "CS_1") (pintype "bidirectional"))
    )
    (net (code "11") (name "GATE_OUT") (class "Default")
      (node (ref "R14") (pin "2") (pinfunction "2_2") (pintype "passive"))
      (node (ref "U1") (pin "58") (pinfunction "RF0_58") (pintype "bidirectional"))
    )
    (net (code "12") (name "GND") (class "Default")
      (node (ref "C1") (pin "1") (pinfunction "1_1") (pintype "passive"))
      (node (ref "C13") (pin "2") (pinfunction "2_2") (pintype "passive"))
      (node (ref "C18") (pin "2") (pinfunction "2_2") (pintype "passive"))
      (node (ref "C19") (pin "1") (pinfunction "1_1") (pintype "passive"))
      (node (ref "C22") (pin "2") (pinfunction "2_2") (pintype "passive"))
      (node (ref "C23") (pin "2") (pinfunction "2_2") (pintype "passive"))
      (node (ref "C28") (pin "1") (pinfunction "1_1") (pintype "passive"))
      (node (ref "C30") (pin "2") (pinfunction "2_2") (pintype "passive"))
      (node (ref "C31") (pin "2") (pinfunction "2_2") (pintype "passive"))
      (node (ref "C32") (pin "1") (pinfunction "1_1") (pintype "passive"))
      (node (ref "C33") (pin "1") (pinfunction "1_1") (pintype "passive"))
      (node (ref "C34") (pin "1") (pinfunction "1_1") (pintype "passive"))
      (node (ref "C38") (pin "1") (pinfunction "1_1") (pintype "passive"))
      (node (ref "C39") (pin "1") (pinfunction "1_1") (pintype "passive"))
      (node (ref "C4") (pin "1") (pinfunction "1_1") (pintype "passive"))
      (node (ref "C40") (pin "1") (pinfunction "1_1") (pintype "passive"))
      (node (ref "C43") (pin "1") (pinfunction "1_1") (pintype "passive"))
      (node (ref "C44") (pin "1") (pinfunction "1_1") (pintype "passive"))
      (node (ref "C5") (pin "1") (pinfunction "1_1") (pintype "passive"))
      (node (ref "C9") (pin "1") (pinfunction "1_1") (pintype "passive"))
      (node (ref "ENCODER") (pin "C") (pinfunction "C_C") (pintype "bidirectional"))
      (node (ref "ENCODER") (pin "E") (pinfunction "E_E") (pintype "bidirectional"))
      (node (ref "EXP1") (pin "1") (pinfunction "1_1") (pintype "passive"))
      (node (ref "EXP2") (pin "1") (pinfunction "1_1") (pintype "passive"))
      (node (ref "POT") (pin "3") (pinfunction "3_3") (pintype "bidirectional"))
      (node (ref "POWER") (pin "P$10") (pinfunction "10_P$10") (pintype "bidirectional"))
      (node (ref "POWER") (pin "P$11") (pinfunction "11_P$11") (pintype "bidirectional"))
      (node (ref "POWER") (pin "P$12") (pinfunction "12_P$12") (pintype "bidirectional"))
      (node (ref "POWER") (pin "P$13") (pinfunction "13_P$13") (pintype "bidirectional"))
      (node (ref "POWER") (pin "P$14") (pinfunction "14_P$14") (pintype "bidirectional"))
      (node (ref "POWER") (pin "P$9") (pinfunction "9_P$9") (pintype "bidirectional"))
      (node (ref "R39") (pin "1") (pinfunction "1_1") (pintype "passive"))
      (node (ref "R40") (pin "1") (pinfunction "1_1") (pintype "passive"))
      (node (ref "TO_SENSOR") (pin "10") (pinfunction "10_10") (pintype "bidirectional"))
      (node (ref "U$11") (pin "1") (pinfunction "DGND_1") (pintype "bidirectional"))
      (node (ref "U$4") (pin "4") (pinfunction "GND_4") (pintype "bidirectional"))
      (node (ref "U1") (pin "20") (pinfunction "AVSS_20") (pintype "bidirectional"))
      (node (ref "U1") (pin "26") (pinfunction "VDD2_26") (pintype "bidirectional"))
      (node (ref "U1") (pin "41") (pinfunction "VSS3_41") (pintype "bidirectional"))
      (node (ref "U1") (pin "9") (pinfunction "VSS_9") (pintype "bidirectional"))
      (node (ref "U3") (pin "2") (pinfunction "GND_2") (pintype "power_in"))
      (node (ref "U3") (pin "4") (pinfunction "GND_4") (pintype "power_in"))
      (node (ref "U4") (pin "4") (pinfunction "VSS_4") (pintype "power_in"))
      (node (ref "U5") (pin "2") (pinfunction "GND_2") (pintype "power_in"))
      (node (ref "U5") (pin "4") (pinfunction "GND_4") (pintype "power_in"))
      (node (ref "U6") (pin "13") (pinfunction "A0_13") (pintype "input"))
      (node (ref "U6") (pin "14") (pinfunction "A1_14") (pintype "input"))
      (node (ref "U6") (pin "15") (pinfunction "ENABLE_15") (pintype "input"))
      (node (ref "U6") (pin "16") (pinfunction "LDAC_16") (pintype "input"))
      (node (ref "U7") (pin "4") (pinfunction "VSS_4") (pintype "power_in"))
      (node (ref "USB") (pin "5") (pinfunction "5_5") (pintype "input"))
    )
    (net (code "13") (name "HOLD") (class "Default")
      (node (ref "R17") (pin "1") (pinfunction "1_1") (pintype "passive"))
      (node (ref "T4") (pin "C") (pinfunction "C_C") (pintype "passive"))
      (node (ref "U1") (pin "55") (pinfunction "RD7_55") (pintype "bidirectional"))
    )
    (net (code "14") (name "I2C1_SCL") (class "Default")
      (node (ref "TO_SENSOR") (pin "2") (pinfunction "2_2") (pintype "bidirectional"))
      (node (ref "U1") (pin "44") (pinfunction "RD10_44") (pintype "bidirectional"))
    )
    (net (code "15") (name "I2C1_SDA") (class "Default")
      (node (ref "TO_SENSOR") (pin "19") (pinfunction "19_19") (pintype "bidirectional"))
      (node (ref "U1") (pin "43") (pinfunction "RD9_43") (pintype "bidirectional"))
    )
    (net (code "16") (name "I2C2_SCL") (class "Default")
      (node (ref "EXP1") (pin "2") (pinfunction "2_2") (pintype "passive"))
      (node (ref "EXP2") (pin "2") (pinfunction "2_2") (pintype "passive"))
      (node (ref "U1") (pin "32") (pinfunction "RF5_32") (pintype "bidirectional"))
    )
    (net (code "17") (name "I2C2_SDA") (class "Default")
      (node (ref "EXP1") (pin "3") (pinfunction "3_3") (pintype "passive"))
      (node (ref "EXP2") (pin "3") (pinfunction "3_3") (pintype "passive"))
      (node (ref "U1") (pin "31") (pinfunction "RF4_31") (pintype "bidirectional"))
    )
    (net (code "18") (name "LED_PWM_1") (class "Default")
      (node (ref "TO_SENSOR") (pin "5") (pinfunction "5_5") (pintype "bidirectional"))
      (node (ref "U1") (pin "49") (pinfunction "RD1_49") (pintype "bidirectional"))
    )
    (net (code "19") (name "LED_PWM_2") (class "Default")
      (node (ref "TO_SENSOR") (pin "16") (pinfunction "16_16") (pintype "bidirectional"))
      (node (ref "U1") (pin "48") (pinfunction "RC14_48") (pintype "bidirectional"))
    )
    (net (code "20") (name "LED_PWM_3") (class "Default")
      (node (ref "TO_SENSOR") (pin "6") (pinfunction "6_6") (pintype "bidirectional"))
      (node (ref "U1") (pin "51") (pinfunction "RD3_51") (pintype "bidirectional"))
    )
    (net (code "21") (name "LED_PWM_4") (class "Default")
      (node (ref "TO_SENSOR") (pin "15") (pinfunction "15_15") (pintype "bidirectional"))
      (node (ref "U1") (pin "52") (pinfunction "RD4_52") (pintype "bidirectional"))
    )
    (net (code "22") (name "LED_PWM_5") (class "Default")
      (node (ref "TO_SENSOR") (pin "7") (pinfunction "7_7") (pintype "bidirectional"))
      (node (ref "U1") (pin "53") (pinfunction "RD5_53") (pintype "bidirectional"))
    )
    (net (code "23") (name "LOOP_SYNC") (class "Default")
      (node (ref "R6") (pin "2") (pinfunction "2_2") (pintype "passive"))
      (node (ref "U1") (pin "61") (pinfunction "RE1_61") (pintype "bidirectional"))
    )
    (net (code "24") (name "MCLR") (class "Default")
      (node (ref "R16") (pin "1") (pinfunction "1_1") (pintype "passive"))
      (node (ref "U$4") (pin "6") (pinfunction "VPP_6") (pintype "bidirectional"))
      (node (ref "U1") (pin "7") (pinfunction "MCLR_7") (pintype "bidirectional"))
    )
    (net (code "25") (name "MGC3130_IRQ") (class "Default")
      (node (ref "TO_SENSOR") (pin "18") (pinfunction "18_18") (pintype "bidirectional"))
      (node (ref "U1") (pin "46") (pinfunction "RD0_46") (pintype "bidirectional"))
    )
    (net (code "26") (name "MGC3130_RESET") (class "Default")
      (node (ref "TO_SENSOR") (pin "3") (pinfunction "3_3") (pintype "bidirectional"))
      (node (ref "U1") (pin "47") (pinfunction "RC13_47") (pintype "bidirectional"))
    )
    (net (code "27") (name "Net-(C32-Pad2)") (class "Default")
      (node (ref "C32") (pin "2") (pinfunction "2_2") (pintype "passive"))
      (node (ref "R15") (pin "1") (pinfunction "1_1") (pintype "passive"))
      (node (ref "R16") (pin "2") (pinfunction "2_2") (pintype "passive"))
    )
    (net (code "28") (name "Net-(D1-C1A2)") (class "Default")
      (node (ref "D1") (pin "3") (pinfunction "C1A2_3") (pintype "passive"))
      (node (ref "R2") (pin "1") (pinfunction "1_1") (pintype "passive"))
      (node (ref "U8") (pin "2") (pinfunction "IN+_2") (pintype "input"))
    )
    (net (code "29") (name "Net-(ENCODER-PadD)") (class "Default")
      (node (ref "ENCODER") (pin "D") (pinfunction "D_D") (pintype "bidirectional"))
      (node (ref "R21") (pin "1") (pinfunction "1_1") (pintype "passive"))
    )
    (net (code "30") (name "Net-(IC1A-+IN)") (class "Default")
      (node (ref "IC1") (pin "3") (pinfunction "+IN_3") (pintype "input"))
      (node (ref "U6") (pin "1") (pinfunction "VOUTA_1") (pintype "input"))
    )
    (net (code "31") (name "Net-(IC1A--IN)") (class "Default")
      (node (ref "C2") (pin "2") (pinfunction "2_2") (pintype "passive"))
      (node (ref "IC1") (pin "2") (pinfunction "-IN_2") (pintype "input"))
      (node (ref "R23") (pin "1") (pinfunction "1_1") (pintype "passive"))
      (node (ref "R25") (pin "1") (pinfunction "1_1") (pintype "passive"))
    )
    (net (code "32") (name "Net-(IC1A-OUT)") (class "Default")
      (node (ref "C2") (pin "1") (pinfunction "1_1") (pintype "passive"))
      (node (ref "IC1") (pin "1") (pinfunction "OUT_1") (pintype "output"))
      (node (ref "R23") (pin "2") (pinfunction "2_2") (pintype "passive"))
      (node (ref "R24") (pin "1") (pinfunction "1_1") (pintype "passive"))
    )
    (net (code "33") (name "Net-(IC1B-+IN)") (class "Default")
      (node (ref "IC1") (pin "5") (pinfunction "+IN_5") (pintype "input"))
      (node (ref "U6") (pin "2") (pinfunction "VOUTB_2") (pintype "input"))
    )
    (net (code "34") (name "Net-(IC1B--IN)") (class "Default")
      (node (ref "C3") (pin "2") (pinfunction "2_2") (pintype "passive"))
      (node (ref "IC1") (pin "6") (pinfunction "-IN_6") (pintype "input"))
      (node (ref "R26") (pin "2") (pinfunction "2_2") (pintype "passive"))
      (node (ref "R27") (pin "2") (pinfunction "2_2") (pintype "passive"))
    )
    (net (code "35") (name "Net-(IC1B-OUT)") (class "Default")
      (node (ref "C3") (pin "1") (pinfunction "1_1") (pintype "passive"))
      (node (ref "IC1") (pin "7") (pinfunction "OUT_7") (pintype "output"))
      (node (ref "R26") (pin "1") (pinfunction "1_1") (pintype "passive"))
      (node (ref "R28") (pin "1") (pinfunction "1_1") (pintype "passive"))
    )
    (net (code "36") (name "Net-(IC1C-+IN)") (class "Default")
      (node (ref "IC1") (pin "10") (pinfunction "+IN_10") (pintype "input"))
      (node (ref "R19") (pin "1") (pinfunction "1_1") (pintype "passive"))
      (node (ref "R20") (pin "2") (pinfunction "2_2") (pintype "passive"))
    )
    (net (code "37") (name "Net-(IC1C--IN)") (class "Default")
      (node (ref "C6") (pin "2") (pinfunction "2_2") (pintype "passive"))
      (node (ref "IC1") (pin "9") (pinfunction "-IN_9") (pintype "input"))
      (node (ref "R1") (pin "1") (pinfunction "1_1") (pintype "passive"))
      (node (ref "R35") (pin "2") (pinfunction "2_2") (pintype "passive"))
    )
    (net (code "38") (name "Net-(IC1C-OUT)") (class "Default")
      (node (ref "C6") (pin "1") (pinfunction "1_1") (pintype "passive"))
      (node (ref "IC1") (pin "8") (pinfunction "OUT_8") (pintype "output"))
      (node (ref "R1") (pin "2") (pinfunction "2_2") (pintype "passive"))
      (node (ref "R2") (pin "2") (pinfunction "2_2") (pintype "passive"))
    )
    (net (code "39") (name "Net-(IC1D-+IN)") (class "Default")
      (node (ref "IC1") (pin "12") (pinfunction "+IN_12") (pintype "input"))
      (node (ref "U6") (pin "7") (pinfunction "VOUTC_7") (pintype "input"))
    )
    (net (code "40") (name "Net-(IC1D--IN)") (class "Default")
      (node (ref "C20") (pin "2") (pinfunction "2_2") (pintype "passive"))
      (node (ref "IC1") (pin "13") (pinfunction "-IN_13") (pintype "input"))
      (node (ref "R29") (pin "1") (pinfunction "1_1") (pintype "passive"))
      (node (ref "R30") (pin "1") (pinfunction "1_1") (pintype "passive"))
    )
    (net (code "41") (name "Net-(IC1D-OUT)") (class "Default")
      (node (ref "C20") (pin "1") (pinfunction "1_1") (pintype "passive"))
      (node (ref "IC1") (pin "14") (pinfunction "OUT_14") (pintype "output"))
      (node (ref "R29") (pin "2") (pinfunction "2_2") (pintype "passive"))
      (node (ref "R31") (pin "1") (pinfunction "1_1") (pintype "passive"))
    )
    (net (code "42") (name "Net-(JACK1-TIP)") (class "Default")
      (node (ref "JACK1") (pin "3") (pinfunction "TIP_3") (pintype "bidirectional"))
      (node (ref "R3") (pin "2") (pinfunction "2_2") (pintype "passive"))
    )
    (net (code "43") (name "Net-(JACK2-TIP)") (class "Default")
      (node (ref "JACK2") (pin "3") (pinfunction "TIP_3") (pintype "bidirectional"))
      (node (ref "R8") (pin "1") (pinfunction "1_1") (pintype "passive"))
    )
    (net (code "44") (name "Net-(JACK3-TIP)") (class "Default")
      (node (ref "JACK3") (pin "3") (pinfunction "TIP_3") (pintype "bidirectional"))
      (node (ref "R11") (pin "2") (pinfunction "2_2") (pintype "passive"))
    )
    (net (code "45") (name "Net-(JACK4-TIP)") (class "Default")
      (node (ref "JACK4") (pin "3") (pinfunction "TIP_3") (pintype "bidirectional"))
      (node (ref "R18") (pin "1") (pinfunction "1_1") (pintype "passive"))
    )
    (net (code "46") (name "Net-(JACK5-TIP)") (class "Default")
      (node (ref "JACK5") (pin "3") (pinfunction "TIP_3") (pintype "bidirectional"))
      (node (ref "R35") (pin "1") (pinfunction "1_1") (pintype "passive"))
    )
    (net (code "47") (name "Net-(JACK6-TIP)") (class "Default")
      (node (ref "JACK6") (pin "3") (pinfunction "TIP_3") (pintype "bidirectional"))
      (node (ref "R24") (pin "2") (pinfunction "2_2") (pintype "passive"))
    )
    (net (code "48") (name "Net-(JACK7-TIP)") (class "Default")
      (node (ref "JACK7") (pin "3") (pinfunction "TIP_3") (pintype "bidirectional"))
      (node (ref "R37") (pin "1") (pinfunction "1_1") (pintype "passive"))
    )
    (net (code "49") (name "Net-(JACK8-TIP)") (class "Default")
      (node (ref "JACK8") (pin "3") (pinfunction "TIP_3") (pintype "bidirectional"))
      (node (ref "R83") (pin "1") (pinfunction "1_1") (pintype "passive"))
    )
    (net (code "50") (name "Net-(JACK9-TIP)") (class "Default")
      (node (ref "JACK9") (pin "3") (pinfunction "TIP_3") (pintype "bidirectional"))
      (node (ref "R28") (pin "2") (pinfunction "2_2") (pintype "passive"))
    )
    (net (code "51") (name "Net-(JACK10-TIP)") (class "Default")
      (node (ref "JACK10") (pin "3") (pinfunction "TIP_3") (pintype "bidirectional"))
      (node (ref "R31") (pin "2") (pinfunction "2_2") (pintype "passive"))
    )
    (net (code "52") (name "Net-(POWER-7)") (class "Default")
      (node (ref "F1") (pin "1") (pinfunction "1_1") (pintype "bidirectional"))
      (node (ref "POWER") (pin "P$7") (pinfunction "7_P$7") (pintype "bidirectional"))
      (node (ref "POWER") (pin "P$8") (pinfunction "8_P$8") (pintype "bidirectional"))
    )
    (net (code "53") (name "Net-(POWER-15)") (class "Default")
      (node (ref "F2") (pin "1") (pinfunction "1_1") (pintype "bidirectional"))
      (node (ref "POWER") (pin "P$15") (pinfunction "15_P$15") (pintype "bidirectional"))
      (node (ref "POWER") (pin "P$16") (pinfunction "16_P$16") (pintype "bidirectional"))
    )
    (net (code "54") (name "Net-(R8-Pad2)") (class "Default")
      (node (ref "R8") (pin "2") (pinfunction "2_2") (pintype "passive"))
      (node (ref "T2") (pin "B") (pinfunction "B_B") (pintype "passive"))
    )
    (net (code "55") (name "Net-(R18-Pad2)") (class "Default")
      (node (ref "R18") (pin "2") (pinfunction "2_2") (pintype "passive"))
      (node (ref "T4") (pin "B") (pinfunction "B_B") (pintype "passive"))
    )
    (net (code "56") (name "Net-(R37-Pad2)") (class "Default")
      (node (ref "R37") (pin "2") (pinfunction "2_2") (pintype "passive"))
      (node (ref "T12") (pin "B") (pinfunction "B_B") (pintype "passive"))
    )
    (net (code "57") (name "Net-(R38-Pad1)") (class "Default")
      (node (ref "R38") (pin "1") (pinfunction "1_1") (pintype "passive"))
      (node (ref "R39") (pin "2") (pinfunction "2_2") (pintype "passive"))
      (node (ref "USB") (pin "1") (pinfunction "1_1") (pintype "input"))
    )
    (net (code "58") (name "Net-(R41-Pad2)") (class "Default")
      (node (ref "R41") (pin "2") (pinfunction "2_2") (pintype "passive"))
      (node (ref "U$2") (pin "2") (pinfunction "2_2") (pintype "bidirectional"))
    )
    (net (code "59") (name "Net-(R83-Pad2)") (class "Default")
      (node (ref "R83") (pin "2") (pinfunction "2_2") (pintype "passive"))
      (node (ref "T13") (pin "B") (pinfunction "B_B") (pintype "passive"))
    )
    (net (code "60") (name "Net-(T1-B)") (class "Default")
      (node (ref "R5") (pin "1") (pinfunction "1_1") (pintype "passive"))
      (node (ref "R6") (pin "1") (pinfunction "1_1") (pintype "passive"))
      (node (ref "T1") (pin "3") (pinfunction "B_3") (pintype "passive"))
    )
    (net (code "61") (name "Net-(T1-C)") (class "Default")
      (node (ref "R3") (pin "1") (pinfunction "1_1") (pintype "passive"))
      (node (ref "R4") (pin "2") (pinfunction "2_2") (pintype "passive"))
      (node (ref "T1") (pin "1") (pinfunction "C_1") (pintype "passive"))
    )
    (net (code "62") (name "Net-(T3-B)") (class "Default")
      (node (ref "R13") (pin "1") (pinfunction "1_1") (pintype "passive"))
      (node (ref "R14") (pin "1") (pinfunction "1_1") (pintype "passive"))
      (node (ref "T3") (pin "3") (pinfunction "B_3") (pintype "passive"))
    )
    (net (code "63") (name "Net-(T3-C)") (class "Default")
      (node (ref "R11") (pin "1") (pinfunction "1_1") (pintype "passive"))
      (node (ref "R12") (pin "2") (pinfunction "2_2") (pintype "passive"))
      (node (ref "T3") (pin "1") (pinfunction "C_1") (pintype "passive"))
    )
    (net (code "64") (name "Net-(U1-OSC1)") (class "Default")
      (node (ref "C31") (pin "1") (pinfunction "1_1") (pintype "passive"))
      (node (ref "CRYSTAL") (pin "1") (pinfunction "1_1") (pintype "bidirectional"))
      (node (ref "U1") (pin "39") (pinfunction "OSC1_39") (pintype "bidirectional"))
    )
    (net (code "65") (name "Net-(U1-OSC2)") (class "Default")
      (node (ref "C23") (pin "1") (pinfunction "1_1") (pintype "passive"))
      (node (ref "CRYSTAL") (pin "3") (pinfunction "3_3") (pintype "bidirectional"))
      (node (ref "U1") (pin "40") (pinfunction "OSC2_40") (pintype "bidirectional"))
    )
    (net (code "66") (name "Net-(U1-RB6)") (class "Default")
      (node (ref "R41") (pin "1") (pinfunction "1_1") (pintype "passive"))
      (node (ref "U1") (pin "17") (pinfunction "RB6_17") (pintype "bidirectional"))
    )
    (net (code "67") (name "Net-(U1-RB7)") (class "Default")
      (node (ref "U$2") (pin "3") (pinfunction "3_3") (pintype "bidirectional"))
      (node (ref "U1") (pin "18") (pinfunction "RB7_18") (pintype "bidirectional"))
    )
    (net (code "68") (name "Net-(U1-RB12)") (class "Default")
      (node (ref "POT") (pin "2") (pinfunction "2_2") (pintype "bidirectional"))
      (node (ref "U1") (pin "27") (pinfunction "RB12_27") (pintype "bidirectional"))
    )
    (net (code "69") (name "Net-(U1-RE3)") (class "Default")
      (node (ref "C4") (pin "2") (pinfunction "2_2") (pintype "passive"))
      (node (ref "ENCODER") (pin "A") (pinfunction "A_A") (pintype "bidirectional"))
      (node (ref "R9") (pin "1") (pinfunction "1_1") (pintype "passive"))
      (node (ref "U1") (pin "63") (pinfunction "RE3_63") (pintype "bidirectional"))
    )
    (net (code "70") (name "Net-(U1-RE4)") (class "Default")
      (node (ref "C5") (pin "2") (pinfunction "2_2") (pintype "passive"))
      (node (ref "ENCODER") (pin "B") (pinfunction "B_B") (pintype "bidirectional"))
      (node (ref "R10") (pin "1") (pinfunction "1_1") (pintype "passive"))
      (node (ref "U1") (pin "64") (pinfunction "RE4_64") (pintype "bidirectional"))
    )
    (net (code "71") (name "Net-(U1-RF3)") (class "Default")
      (node (ref "U1") (pin "33") (pinfunction "RF3_33") (pintype "bidirectional"))
      (node (ref "USB") (pin "4") (pinfunction "4_4") (pintype "input"))
    )
    (net (code "72") (name "Net-(U1-VBUS)") (class "Default")
      (node (ref "R38") (pin "2") (pinfunction "2_2") (pintype "passive"))
      (node (ref "U1") (pin "34") (pinfunction "VBUS_34") (pintype "bidirectional"))
    )
    (net (code "73") (name "Net-(U1-VCAP)") (class "Default")
      (node (ref "C43") (pin "2") (pinfunction "2_2") (pintype "passive"))
      (node (ref "U1") (pin "56") (pinfunction "VCAP_56") (pintype "bidirectional"))
    )
    (net (code "74") (name "PGEC") (class "Default")
      (node (ref "U$4") (pin "2") (pinfunction "PGC_2") (pintype "bidirectional"))
      (node (ref "U1") (pin "15") (pinfunction "RB1_15") (pintype "bidirectional"))
    )
    (net (code "75") (name "PGED") (class "Default")
      (node (ref "U$4") (pin "3") (pinfunction "PGD_3") (pintype "bidirectional"))
      (node (ref "U1") (pin "16") (pinfunction "RB0_16") (pintype "bidirectional"))
    )
    (net (code "76") (name "RAM_SS") (class "Default")
      (node (ref "U1") (pin "21") (pinfunction "RB8_21") (pintype "bidirectional"))
      (node (ref "U4") (pin "1") (pinfunction "CS_1") (pintype "bidirectional"))
    )
    (net (code "77") (name "RECORD_IN") (class "Default")
      (node (ref "R36") (pin "1") (pinfunction "1_1") (pintype "passive"))
      (node (ref "T12") (pin "C") (pinfunction "C_C") (pintype "passive"))
      (node (ref "U1") (pin "62") (pinfunction "RE2_62") (pintype "bidirectional"))
    )
    (net (code "78") (name "SPI1_CLK") (class "Default")
      (node (ref "U1") (pin "50") (pinfunction "RD2_50") (pintype "bidirectional"))
      (node (ref "U6") (pin "10") (pinfunction "SCLK_10") (pintype "input"))
      (node (ref "U8") (pin "7") (pinfunction "CLK_7") (pintype "input"))
    )
    (net (code "79") (name "SPI1_MOSI") (class "Default")
      (node (ref "U1") (pin "5") (pinfunction "RG7_5") (pintype "bidirectional"))
      (node (ref "U6") (pin "11") (pinfunction "DIN_11") (pintype "input"))
      (node (ref "U8") (pin "6") (pinfunction "DOUT_6") (pintype "output"))
    )
    (net (code "80") (name "SPI2_MISO") (class "Default")
      (node (ref "U1") (pin "6") (pinfunction "RG8_6") (pintype "bidirectional"))
      (node (ref "U4") (pin "2") (pinfunction "SO/SIO1_2") (pintype "bidirectional"))
      (node (ref "U7") (pin "2") (pinfunction "SO_2") (pintype "bidirectional"))
    )
    (net (code "81") (name "SPI2_MOSI") (class "Default")
      (node (ref "U1") (pin "14") (pinfunction "RB2_14") (pintype "bidirectional"))
      (node (ref "U4") (pin "5") (pinfunction "SI/SIO0_5") (pintype "bidirectional"))
      (node (ref "U7") (pin "5") (pinfunction "SI_5") (pintype "bidirectional"))
    )
    (net (code "82") (name "SPI2_SCK") (class "Default")
      (node (ref "U1") (pin "4") (pinfunction "RG6_4") (pintype "bidirectional"))
      (node (ref "U4") (pin "6") (pinfunction "SCK_6") (pintype "bidirectional"))
      (node (ref "U7") (pin "6") (pinfunction "SCK_6") (pintype "bidirectional"))
    )
    (net (code "83") (name "SR_CLK") (class "Default")
      (node (ref "TO_SENSOR") (pin "17") (pinfunction "17_17") (pintype "bidirectional"))
      (node (ref "U1") (pin "12") (pinfunction "RB4_12") (pintype "bidirectional"))
    )
    (net (code "84") (name "SR_DATA") (class "Default")
      (node (ref "TO_SENSOR") (pin "4") (pinfunction "4_4") (pintype "bidirectional"))
      (node (ref "U1") (pin "11") (pinfunction "RB5_11") (pintype "bidirectional"))
    )
    (net (code "85") (name "SWITCH_INPUT") (class "Default")
      (node (ref "R40") (pin "2") (pinfunction "2_2") (pintype "passive"))
      (node (ref "U$2") (pin "4") (pinfunction "4_4") (pintype "bidirectional"))
      (node (ref "U1") (pin "45") (pinfunction "RD11_45") (pintype "bidirectional"))
    )
    (net (code "86") (name "SYNC_IN") (class "Default")
      (node (ref "R82") (pin "1") (pinfunction "1_1") (pintype "passive"))
      (node (ref "T13") (pin "C") (pinfunction "C_C") (pintype "passive"))
      (node (ref "U1") (pin "59") (pinfunction "RF1_59") (pintype "bidirectional"))
    )
    (net (code "87") (name "VCC") (class "Default")
      (node (ref "C18") (pin "1") (pinfunction "1_1") (pintype "passive"))
      (node (ref "C19") (pin "2") (pinfunction "2_2") (pintype "passive"))
      (node (ref "C24") (pin "2") (pinfunction "2_2") (pintype "passive"))
      (node (ref "C25") (pin "2") (pinfunction "2_2") (pintype "passive"))
      (node (ref "C28") (pin "2") (pinfunction "2_2") (pintype "passive"))
      (node (ref "C37") (pin "2") (pinfunction "2_2") (pintype "passive"))
      (node (ref "F1") (pin "2") (pinfunction "2_2") (pintype "bidirectional"))
      (node (ref "IC1") (pin "4") (pinfunction "V+_4") (pintype "power_in"))
      (node (ref "U2") (pin "1") (pinfunction "I_1") (pintype "input"))
      (node (ref "U3") (pin "1") (pinfunction "I_1") (pintype "input"))
      (node (ref "U5") (pin "1") (pinfunction "I_1") (pintype "input"))
    )
    (net (code "88") (name "VEE") (class "Default")
      (node (ref "C24") (pin "1") (pinfunction "1_1") (pintype "passive"))
      (node (ref "C25") (pin "1") (pinfunction "1_1") (pintype "passive"))
      (node (ref "F2") (pin "2") (pinfunction "2_2") (pintype "bidirectional"))
      (node (ref "IC1") (pin "11") (pinfunction "V-_11") (pintype "power_in"))
    )
    (net (code "89") (name "unconnected-(POWER-1-PadP$1)") (class "Default")
      (node (ref "POWER") (pin "P$1") (pinfunction "1_P$1") (pintype "bidirectional"))
    )
    (net (code "90") (name "unconnected-(POWER-2-PadP$2)") (class "Default")
      (node (ref "POWER") (pin "P$2") (pinfunction "2_P$2") (pintype "bidirectional"))
    )
    (net (code "91") (name "unconnected-(POWER-3-PadP$3)") (class "Default")
      (node (ref "POWER") (pin "P$3") (pinfunction "3_P$3") (pintype "bidirectional"))
    )
    (net (code "92") (name "unconnected-(POWER-4-PadP$4)") (class "Default")
      (node (ref "POWER") (pin "P$4") (pinfunction "4_P$4") (pintype "bidirectional"))
    )
    (net (code "93") (name "unconnected-(POWER-5-PadP$5)") (class "Default")
      (node (ref "POWER") (pin "P$5") (pinfunction "5_P$5") (pintype "bidirectional"))
    )
    (net (code "94") (name "unconnected-(POWER-6-PadP$6)") (class "Default")
      (node (ref "POWER") (pin "P$6") (pinfunction "6_P$6") (pintype "bidirectional"))
    )
    (net (code "95") (name "unconnected-(TO_SENSOR-Pad8)") (class "Default")
      (node (ref "TO_SENSOR") (pin "8") (pinfunction "8_8") (pintype "bidirectional"))
    )
    (net (code "96") (name "unconnected-(TO_SENSOR-Pad9)") (class "Default")
      (node (ref "TO_SENSOR") (pin "9") (pinfunction "9_9") (pintype "bidirectional"))
    )
    (net (code "97") (name "unconnected-(TO_SENSOR-Pad12)") (class "Default")
      (node (ref "TO_SENSOR") (pin "12") (pinfunction "12_12") (pintype "bidirectional"))
    )
    (net (code "98") (name "unconnected-(TO_SENSOR-Pad13)") (class "Default")
      (node (ref "TO_SENSOR") (pin "13") (pinfunction "13_13") (pintype "bidirectional"))
    )
    (net (code "99") (name "unconnected-(TO_SENSOR-Pad14)") (class "Default")
      (node (ref "TO_SENSOR") (pin "14") (pinfunction "14_14") (pintype "bidirectional"))
    )
    (net (code "100") (name "unconnected-(U$4-PGM-Pad1)") (class "Default")
      (node (ref "U$4") (pin "1") (pinfunction "PGM_1") (pintype "bidirectional"))
    )
    (net (code "101") (name "unconnected-(U$11-IN-Pad3)") (class "Default")
      (node (ref "U$11") (pin "3") (pinfunction "IN_3") (pintype "bidirectional"))
    )
    (net (code "102") (name "unconnected-(U1-RB9-Pad22)") (class "Default")
      (node (ref "U1") (pin "22") (pinfunction "RB9_22") (pintype "bidirectional"))
    )
    (net (code "103") (name "unconnected-(U1-RB10-Pad23)") (class "Default")
      (node (ref "U1") (pin "23") (pinfunction "RB10_23") (pintype "bidirectional"))
    )
    (net (code "104") (name "unconnected-(U1-RB11-Pad24)") (class "Default")
      (node (ref "U1") (pin "24") (pinfunction "RB11_24") (pintype "bidirectional"))
    )
    (net (code "105") (name "unconnected-(U1-RB14-Pad29)") (class "Default")
      (node (ref "U1") (pin "29") (pinfunction "RB14_29") (pintype "bidirectional"))
    )
    (net (code "106") (name "unconnected-(U1-RB15-Pad30)") (class "Default")
      (node (ref "U1") (pin "30") (pinfunction "RB15_30") (pintype "bidirectional"))
    )
    (net (code "107") (name "unconnected-(U1-RD6-Pad54)") (class "Default")
      (node (ref "U1") (pin "54") (pinfunction "RD6_54") (pintype "bidirectional"))
    )
    (net (code "108") (name "unconnected-(U1-RD8-Pad42)") (class "Default")
      (node (ref "U1") (pin "42") (pinfunction "RD8_42") (pintype "bidirectional"))
    )
    (net (code "109") (name "unconnected-(U1-RE6-Pad2)") (class "Default")
      (node (ref "U1") (pin "2") (pinfunction "RE6_2") (pintype "bidirectional"))
    )
    (net (code "110") (name "unconnected-(U1-RE7-Pad3)") (class "Default")
      (node (ref "U1") (pin "3") (pinfunction "RE7_3") (pintype "bidirectional"))
    )
    (net (code "111") (name "unconnected-(U1-RG9-Pad8)") (class "Default")
      (node (ref "U1") (pin "8") (pinfunction "RG9_8") (pintype "bidirectional"))
    )
    (net (code "112") (name "unconnected-(U4-SIO2-Pad3)") (class "Default")
      (node (ref "U4") (pin "3") (pinfunction "SIO2_3") (pintype "bidirectional"))
    )
    (net (code "113") (name "unconnected-(U6-VOUTD-Pad8)") (class "Default")
      (node (ref "U6") (pin "8") (pinfunction "VOUTD_8") (pintype "input"))
    )
  )
)
